# 08D-005.net
KiCad netlist of a schematic drawn in EAGLE
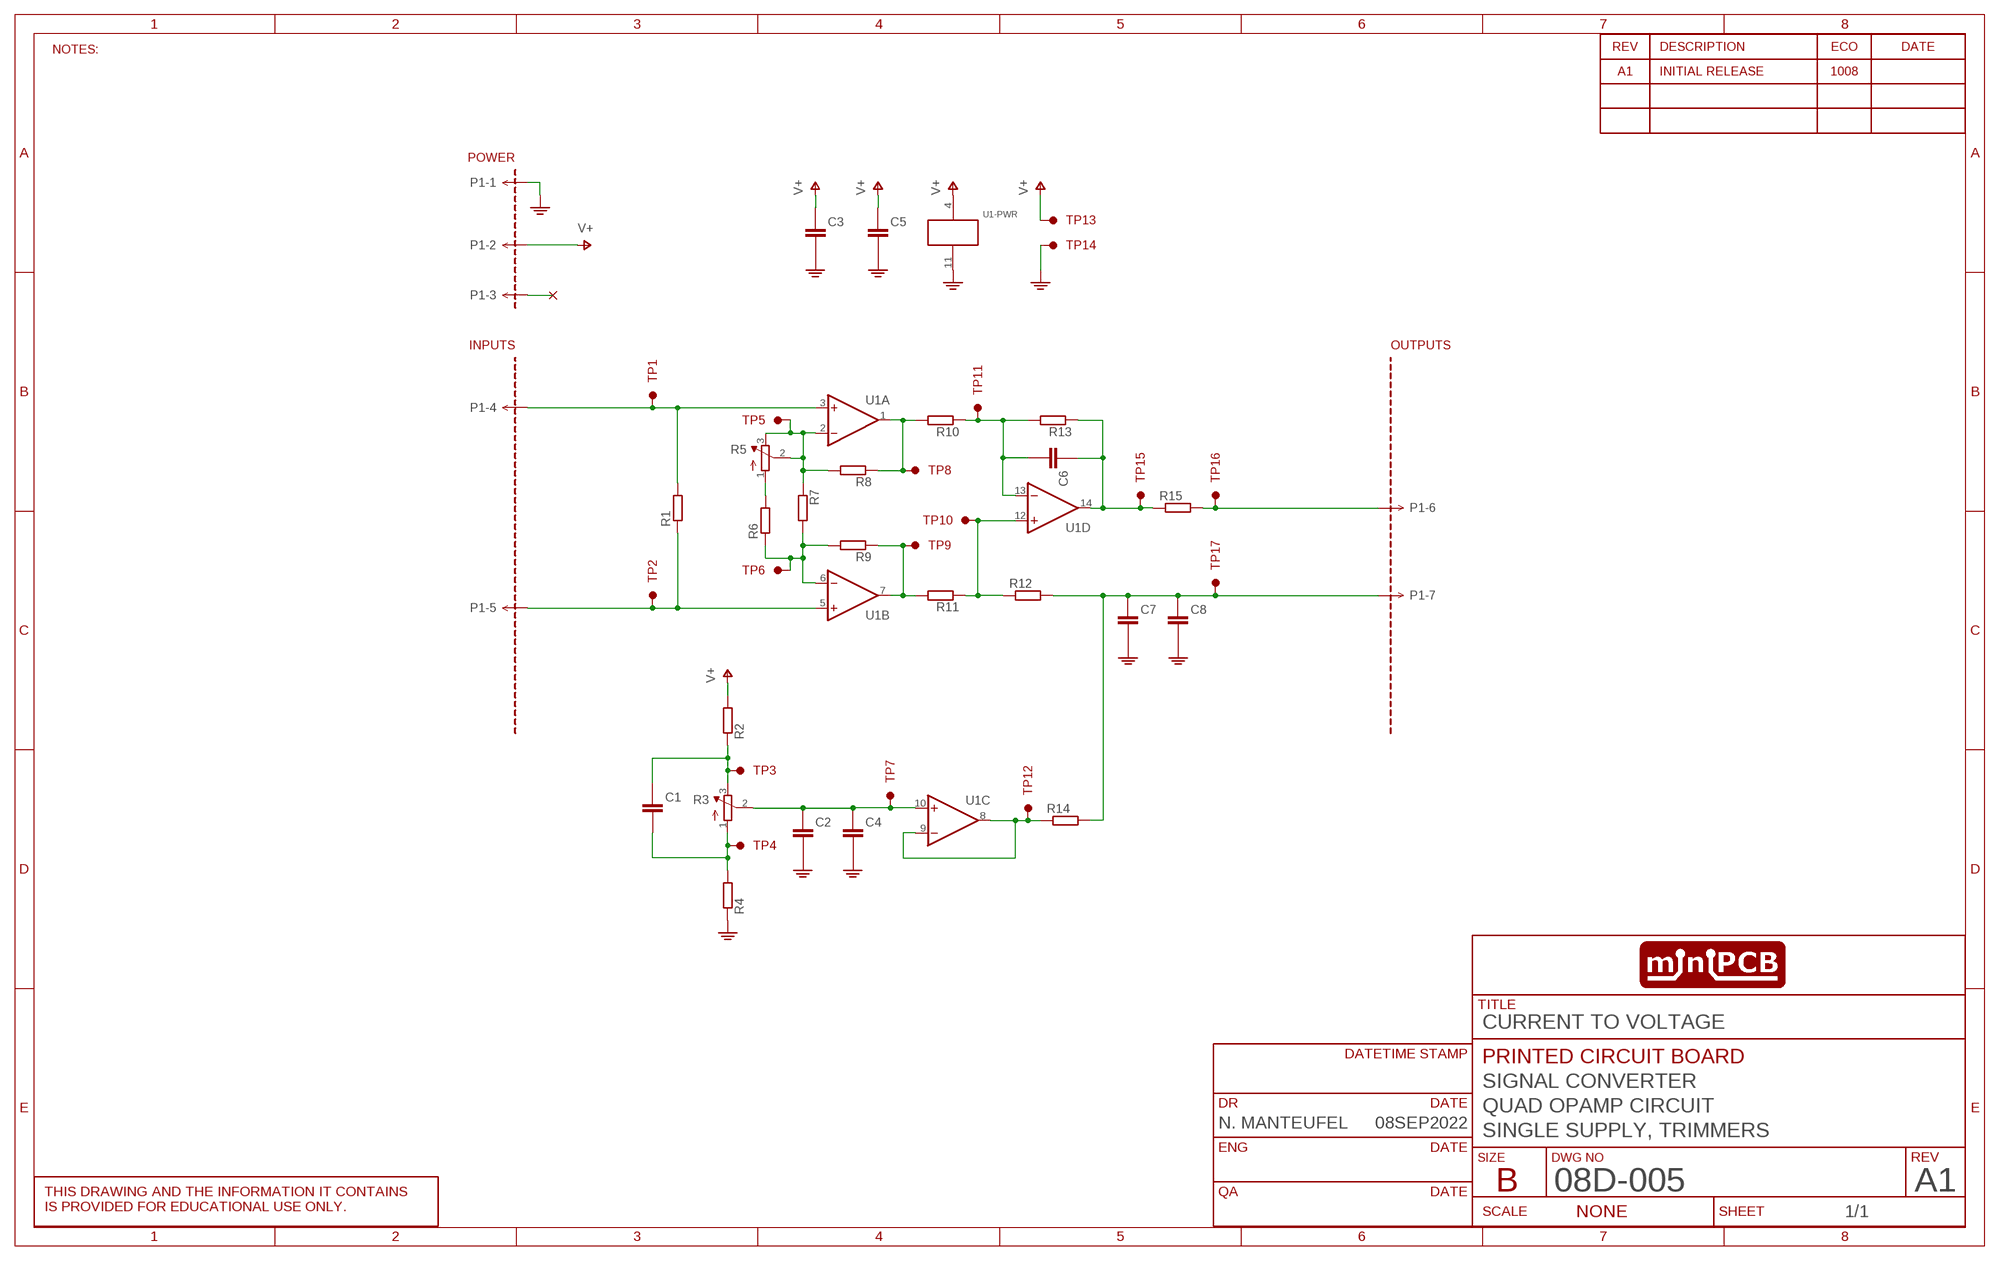
[diagram p0: schematic, sheet 1]

(export (version "E")
  (design (tool "Eeschema 10.0.6"))
  (components
    (comp (ref "C1")
      (value "CAPACITORTHD")
      (footprint "eagle-import:C050-024X044")
      (libsource (lib "eagle-import") (part "CAPACITORTHD"))
    )
    (comp (ref "C2")
      (value "CAPACITORTHD")
      (footprint "eagle-import:C050-024X044")
      (libsource (lib "eagle-import") (part "CAPACITORTHD"))
    )
    (comp (ref "C3")
      (value "CAPACITORTHD")
      (footprint "eagle-import:C050-024X044")
      (libsource (lib "eagle-import") (part "CAPACITORTHD"))
    )
    (comp (ref "C4")
      (value "CAPACITOR_10")
      (footprint "eagle-import:C5MM")
      (libsource (lib "eagle-import") (part "CAPACITOR_10"))
    )
    (comp (ref "C5")
      (value "CAPACITOR_10")
      (footprint "eagle-import:C5MM")
      (libsource (lib "eagle-import") (part "CAPACITOR_10"))
    )
    (comp (ref "C6")
      (value "CAPACITORTHD")
      (footprint "eagle-import:C050-024X044")
      (libsource (lib "eagle-import") (part "CAPACITORTHD"))
    )
    (comp (ref "C7")
      (value "CAPACITORTHD")
      (footprint "eagle-import:C050-024X044")
      (libsource (lib "eagle-import") (part "CAPACITORTHD"))
    )
    (comp (ref "C8")
      (value "CAPACITOR_10")
      (footprint "eagle-import:C5MM")
      (libsource (lib "eagle-import") (part "CAPACITOR_10"))
    )
    (comp (ref "P1")
      (value "MINIPCB_7P")
      (footprint "eagle-import:PINS_1X7")
      (libsource (lib "eagle-import") (part "MINIPCB_7P"))
    )
    (comp (ref "PCB1")
      (value "MINIPCB_0P50X75")
      (footprint "eagle-import:MINIPCB_0P_50X75")
      (fields
        (field (name "CIRCUIT_CATEGORY") "SIGNAL CONVERTER")
        (field (name "PART_NUMBER") "08D-005")
        (field (name "REVISION") "A1-01")
        (field (name "TITLE") "CURRENT TO VOLTAGE")
      )
      (libsource (lib "eagle-import") (part "MINIPCB_0P50X75"))
    )
    (comp (ref "R1")
      (value "RESISTOR10MM")
      (footprint "eagle-import:0207_10")
      (libsource (lib "eagle-import") (part "RESISTOR10MM"))
    )
    (comp (ref "R2")
      (value "RESISTOR10MM")
      (footprint "eagle-import:0207_10")
      (libsource (lib "eagle-import") (part "RESISTOR10MM"))
    )
    (comp (ref "R3")
      (value "TRIMPOT0.100THD")
      (footprint "eagle-import:TRIM_0100")
      (libsource (lib "eagle-import") (part "TRIMPOT0.100THD"))
    )
    (comp (ref "R4")
      (value "RESISTOR10MM")
      (footprint "eagle-import:0207_10")
      (libsource (lib "eagle-import") (part "RESISTOR10MM"))
    )
    (comp (ref "R5")
      (value "TRIMPOT0.100THD")
      (footprint "eagle-import:TRIM_0100")
      (libsource (lib "eagle-import") (part "TRIMPOT0.100THD"))
    )
    (comp (ref "R6")
      (value "RESISTOR10MM")
      (footprint "eagle-import:0207_10")
      (libsource (lib "eagle-import") (part "RESISTOR10MM"))
    )
    (comp (ref "R7")
      (value "RESISTOR10MM")
      (footprint "eagle-import:0207_10")
      (libsource (lib "eagle-import") (part "RESISTOR10MM"))
    )
    (comp (ref "R8")
      (value "RESISTOR10MM")
      (footprint "eagle-import:0207_10")
      (libsource (lib "eagle-import") (part "RESISTOR10MM"))
    )
    (comp (ref "R9")
      (value "RESISTOR10MM")
      (footprint "eagle-import:0207_10")
      (libsource (lib "eagle-import") (part "RESISTOR10MM"))
    )
    (comp (ref "R10")
      (value "RESISTOR10MM")
      (footprint "eagle-import:0207_10")
      (libsource (lib "eagle-import") (part "RESISTOR10MM"))
    )
    (comp (ref "R11")
      (value "RESISTOR10MM")
      (footprint "eagle-import:0207_10")
      (libsource (lib "eagle-import") (part "RESISTOR10MM"))
    )
    (comp (ref "R12")
      (value "RESISTOR10MM")
      (footprint "eagle-import:0207_10")
      (libsource (lib "eagle-import") (part "RESISTOR10MM"))
    )
    (comp (ref "R13")
      (value "RESISTOR10MM")
      (footprint "eagle-import:0207_10")
      (libsource (lib "eagle-import") (part "RESISTOR10MM"))
    )
    (comp (ref "R14")
      (value "RESISTOR10MM")
      (footprint "eagle-import:0207_10")
      (libsource (lib "eagle-import") (part "RESISTOR10MM"))
    )
    (comp (ref "R15")
      (value "RESISTOR10MM")
      (footprint "eagle-import:0207_10")
      (libsource (lib "eagle-import") (part "RESISTOR10MM"))
    )
    (comp (ref "TP1")
      (value "TESTPOINTKE5000-SMTEXT")
      (footprint "eagle-import:PINS_1_TESTPOINT_KE5000_NOTEXT")
      (libsource (lib "eagle-import") (part "TESTPOINTKE5000-SMTEXT"))
    )
    (comp (ref "TP2")
      (value "TESTPOINTKE5000-SMTEXT")
      (footprint "eagle-import:PINS_1_TESTPOINT_KE5000_NOTEXT")
      (libsource (lib "eagle-import") (part "TESTPOINTKE5000-SMTEXT"))
    )
    (comp (ref "TP3")
      (value "TESTPOINTKE5000-SMTEXT")
      (footprint "eagle-import:PINS_1_TESTPOINT_KE5000_NOTEXT")
      (libsource (lib "eagle-import") (part "TESTPOINTKE5000-SMTEXT"))
    )
    (comp (ref "TP4")
      (value "TESTPOINTKE5000-SMTEXT")
      (footprint "eagle-import:PINS_1_TESTPOINT_KE5000_NOTEXT")
      (libsource (lib "eagle-import") (part "TESTPOINTKE5000-SMTEXT"))
    )
    (comp (ref "TP5")
      (value "TESTPOINTKE5000-SMTEXT")
      (footprint "eagle-import:PINS_1_TESTPOINT_KE5000_NOTEXT")
      (libsource (lib "eagle-import") (part "TESTPOINTKE5000-SMTEXT"))
    )
    (comp (ref "TP6")
      (value "TESTPOINTKE5000-SMTEXT")
      (footprint "eagle-import:PINS_1_TESTPOINT_KE5000_NOTEXT")
      (libsource (lib "eagle-import") (part "TESTPOINTKE5000-SMTEXT"))
    )
    (comp (ref "TP7")
      (value "TESTPOINTKE5000-SMTEXT")
      (footprint "eagle-import:PINS_1_TESTPOINT_KE5000_NOTEXT")
      (libsource (lib "eagle-import") (part "TESTPOINTKE5000-SMTEXT"))
    )
    (comp (ref "TP8")
      (value "TESTPOINTKE5000-SMTEXT")
      (footprint "eagle-import:PINS_1_TESTPOINT_KE5000_NOTEXT")
      (libsource (lib "eagle-import") (part "TESTPOINTKE5000-SMTEXT"))
    )
    (comp (ref "TP9")
      (value "TESTPOINTKE5000-SMTEXT")
      (footprint "eagle-import:PINS_1_TESTPOINT_KE5000_NOTEXT")
      (libsource (lib "eagle-import") (part "TESTPOINTKE5000-SMTEXT"))
    )
    (comp (ref "TP10")
      (value "TESTPOINTKE5000-SMTEXT")
      (footprint "eagle-import:PINS_1_TESTPOINT_KE5000_NOTEXT")
      (libsource (lib "eagle-import") (part "TESTPOINTKE5000-SMTEXT"))
    )
    (comp (ref "TP11")
      (value "TESTPOINTKE5000-SMTEXT")
      (footprint "eagle-import:PINS_1_TESTPOINT_KE5000_NOTEXT")
      (libsource (lib "eagle-import") (part "TESTPOINTKE5000-SMTEXT"))
    )
    (comp (ref "TP12")
      (value "TESTPOINTKE5000-SMTEXT")
      (footprint "eagle-import:PINS_1_TESTPOINT_KE5000_NOTEXT")
      (libsource (lib "eagle-import") (part "TESTPOINTKE5000-SMTEXT"))
    )
    (comp (ref "TP13")
      (value "TESTPOINTKE5000-SMTEXT")
      (footprint "eagle-import:PINS_1_TESTPOINT_KE5000_NOTEXT")
      (libsource (lib "eagle-import") (part "TESTPOINTKE5000-SMTEXT"))
    )
    (comp (ref "TP14")
      (value "TESTPOINTKE5000-SMTEXT")
      (footprint "eagle-import:PINS_1_TESTPOINT_KE5000_NOTEXT")
      (libsource (lib "eagle-import") (part "TESTPOINTKE5000-SMTEXT"))
    )
    (comp (ref "TP15")
      (value "TESTPOINTKE5000-SMTEXT")
      (footprint "eagle-import:PINS_1_TESTPOINT_KE5000_NOTEXT")
      (libsource (lib "eagle-import") (part "TESTPOINTKE5000-SMTEXT"))
    )
    (comp (ref "TP16")
      (value "TESTPOINTKE5000-SMTEXT")
      (footprint "eagle-import:PINS_1_TESTPOINT_KE5000_NOTEXT")
      (libsource (lib "eagle-import") (part "TESTPOINTKE5000-SMTEXT"))
    )
    (comp (ref "TP17")
      (value "TESTPOINTKE5000-SMTEXT")
      (footprint "eagle-import:PINS_1_TESTPOINT_KE5000_NOTEXT")
      (libsource (lib "eagle-import") (part "TESTPOINTKE5000-SMTEXT"))
    )
    (comp (ref "U1")
      (value "OPAMP_QUADTHD")
      (footprint "eagle-import:DIL14")
      (libsource (lib "eagle-import") (part "OPAMP_QUADTHD"))
    )
  )
  (nets
    (net (code "1") (name "GND") (class "Default")
      (node (ref "C2") (pin "2") (pinfunction "-_2") (pintype "passive"))
      (node (ref "C3") (pin "2") (pinfunction "-_2") (pintype "passive"))
      (node (ref "C4") (pin "-") (pinfunction "-_-") (pintype "passive"))
      (node (ref "C5") (pin "-") (pinfunction "-_-") (pintype "passive"))
      (node (ref "C7") (pin "2") (pinfunction "-_2") (pintype "passive"))
      (node (ref "C8") (pin "-") (pinfunction "-_-") (pintype "passive"))
      (node (ref "P1") (pin "1") (pinfunction "1_1") (pintype "bidirectional"))
      (node (ref "R4") (pin "1") (pinfunction "1_1") (pintype "passive"))
      (node (ref "TP14") (pin "1") (pinfunction "1_1") (pintype "bidirectional"))
      (node (ref "U1") (pin "11") (pinfunction "V-_11") (pintype "power_in"))
    )
    (net (code "2") (name "Net-(C1-+)") (class "Default")
      (node (ref "C1") (pin "1") (pinfunction "+_1") (pintype "passive"))
      (node (ref "R2") (pin "1") (pinfunction "1_1") (pintype "passive"))
      (node (ref "R3") (pin "3") (pinfunction "E_3") (pintype "passive"))
      (node (ref "TP3") (pin "1") (pinfunction "1_1") (pintype "bidirectional"))
    )
    (net (code "3") (name "Net-(C1--)") (class "Default")
      (node (ref "C1") (pin "2") (pinfunction "-_2") (pintype "passive"))
      (node (ref "R3") (pin "1") (pinfunction "A_1") (pintype "passive"))
      (node (ref "R4") (pin "2") (pinfunction "2_2") (pintype "passive"))
      (node (ref "TP4") (pin "1") (pinfunction "1_1") (pintype "bidirectional"))
    )
    (net (code "4") (name "Net-(C2-+)") (class "Default")
      (node (ref "C2") (pin "1") (pinfunction "+_1") (pintype "passive"))
      (node (ref "C4") (pin "+") (pinfunction "+_+") (pintype "passive"))
      (node (ref "R3") (pin "2") (pinfunction "S_2") (pintype "passive"))
      (node (ref "TP7") (pin "1") (pinfunction "1_1") (pintype "bidirectional"))
      (node (ref "U1") (pin "10") (pinfunction "+IN_10") (pintype "input"))
    )
    (net (code "5") (name "Net-(C6-+)") (class "Default")
      (node (ref "C6") (pin "1") (pinfunction "+_1") (pintype "passive"))
      (node (ref "R13") (pin "1") (pinfunction "1_1") (pintype "passive"))
      (node (ref "R15") (pin "1") (pinfunction "1_1") (pintype "passive"))
      (node (ref "TP15") (pin "1") (pinfunction "1_1") (pintype "bidirectional"))
      (node (ref "U1") (pin "14") (pinfunction "OUT_14") (pintype "output"))
    )
    (net (code "6") (name "Net-(C6--)") (class "Default")
      (node (ref "C6") (pin "2") (pinfunction "-_2") (pintype "passive"))
      (node (ref "R10") (pin "1") (pinfunction "1_1") (pintype "passive"))
      (node (ref "R13") (pin "2") (pinfunction "2_2") (pintype "passive"))
      (node (ref "TP11") (pin "1") (pinfunction "1_1") (pintype "bidirectional"))
      (node (ref "U1") (pin "13") (pinfunction "-IN_13") (pintype "input"))
    )
    (net (code "7") (name "Net-(C7-+)") (class "Default")
      (node (ref "C7") (pin "1") (pinfunction "+_1") (pintype "passive"))
      (node (ref "C8") (pin "+") (pinfunction "+_+") (pintype "passive"))
      (node (ref "P1") (pin "7") (pinfunction "1_7") (pintype "bidirectional"))
      (node (ref "R12") (pin "2") (pinfunction "2_2") (pintype "passive"))
      (node (ref "R14") (pin "2") (pinfunction "2_2") (pintype "passive"))
      (node (ref "TP17") (pin "1") (pinfunction "1_1") (pintype "bidirectional"))
    )
    (net (code "8") (name "Net-(P1D-1)") (class "Default")
      (node (ref "P1") (pin "4") (pinfunction "1_4") (pintype "bidirectional"))
      (node (ref "R1") (pin "2") (pinfunction "2_2") (pintype "passive"))
      (node (ref "TP1") (pin "1") (pinfunction "1_1") (pintype "bidirectional"))
      (node (ref "U1") (pin "3") (pinfunction "+IN_3") (pintype "input"))
    )
    (net (code "9") (name "Net-(P1E-1)") (class "Default")
      (node (ref "P1") (pin "5") (pinfunction "1_5") (pintype "bidirectional"))
      (node (ref "R1") (pin "1") (pinfunction "1_1") (pintype "passive"))
      (node (ref "TP2") (pin "1") (pinfunction "1_1") (pintype "bidirectional"))
      (node (ref "U1") (pin "5") (pinfunction "+IN_5") (pintype "input"))
    )
    (net (code "10") (name "Net-(P1F-1)") (class "Default")
      (node (ref "P1") (pin "6") (pinfunction "1_6") (pintype "bidirectional"))
      (node (ref "R15") (pin "2") (pinfunction "2_2") (pintype "passive"))
      (node (ref "TP16") (pin "1") (pinfunction "1_1") (pintype "bidirectional"))
    )
    (net (code "11") (name "Net-(R5-A)") (class "Default")
      (node (ref "R5") (pin "1") (pinfunction "A_1") (pintype "passive"))
      (node (ref "R6") (pin "2") (pinfunction "2_2") (pintype "passive"))
    )
    (net (code "12") (name "Net-(R5-E)") (class "Default")
      (node (ref "R5") (pin "2") (pinfunction "S_2") (pintype "passive"))
      (node (ref "R5") (pin "3") (pinfunction "E_3") (pintype "passive"))
      (node (ref "R7") (pin "1") (pinfunction "1_1") (pintype "passive"))
      (node (ref "R8") (pin "2") (pinfunction "2_2") (pintype "passive"))
      (node (ref "TP5") (pin "1") (pinfunction "1_1") (pintype "bidirectional"))
      (node (ref "U1") (pin "2") (pinfunction "-IN_2") (pintype "input"))
    )
    (net (code "13") (name "Net-(U1B-OUT)") (class "Default")
      (node (ref "R10") (pin "2") (pinfunction "2_2") (pintype "passive"))
      (node (ref "R8") (pin "1") (pinfunction "1_1") (pintype "passive"))
      (node (ref "TP8") (pin "1") (pinfunction "1_1") (pintype "bidirectional"))
      (node (ref "U1") (pin "1") (pinfunction "OUT_1") (pintype "output"))
    )
    (net (code "14") (name "Net-(U1C--IN)") (class "Default")
      (node (ref "R6") (pin "1") (pinfunction "1_1") (pintype "passive"))
      (node (ref "R7") (pin "2") (pinfunction "2_2") (pintype "passive"))
      (node (ref "R9") (pin "2") (pinfunction "2_2") (pintype "passive"))
      (node (ref "TP6") (pin "1") (pinfunction "1_1") (pintype "bidirectional"))
      (node (ref "U1") (pin "6") (pinfunction "-IN_6") (pintype "input"))
    )
    (net (code "15") (name "Net-(U1C-OUT)") (class "Default")
      (node (ref "R11") (pin "2") (pinfunction "2_2") (pintype "passive"))
      (node (ref "R9") (pin "1") (pinfunction "1_1") (pintype "passive"))
      (node (ref "TP9") (pin "1") (pinfunction "1_1") (pintype "bidirectional"))
      (node (ref "U1") (pin "7") (pinfunction "OUT_7") (pintype "output"))
    )
    (net (code "16") (name "Net-(U1D--IN)") (class "Default")
      (node (ref "R14") (pin "1") (pinfunction "1_1") (pintype "passive"))
      (node (ref "TP12") (pin "1") (pinfunction "1_1") (pintype "bidirectional"))
      (node (ref "U1") (pin "8") (pinfunction "OUT_8") (pintype "output"))
      (node (ref "U1") (pin "9") (pinfunction "-IN_9") (pintype "input"))
    )
    (net (code "17") (name "Net-(U1E-+IN)") (class "Default")
      (node (ref "R11") (pin "1") (pinfunction "1_1") (pintype "passive"))
      (node (ref "R12") (pin "1") (pinfunction "1_1") (pintype "passive"))
      (node (ref "TP10") (pin "1") (pinfunction "1_1") (pintype "bidirectional"))
      (node (ref "U1") (pin "12") (pinfunction "+IN_12") (pintype "input"))
    )
    (net (code "18") (name "V+") (class "Default")
      (node (ref "C3") (pin "1") (pinfunction "+_1") (pintype "passive"))
      (node (ref "C5") (pin "+") (pinfunction "+_+") (pintype "passive"))
      (node (ref "P1") (pin "2") (pinfunction "1_2") (pintype "bidirectional"))
      (node (ref "R2") (pin "2") (pinfunction "2_2") (pintype "passive"))
      (node (ref "TP13") (pin "1") (pinfunction "1_1") (pintype "bidirectional"))
      (node (ref "U1") (pin "4") (pinfunction "V+_4") (pintype "power_in"))
    )
    (net (code "19") (name "unconnected-(P1C-1-Pad3)") (class "Default")
      (node (ref "P1") (pin "3") (pinfunction "1_3") (pintype "bidirectional"))
    )
  )
)
